# Motherboard.net
KiCad netlist of a schematic drawn in EAGLE
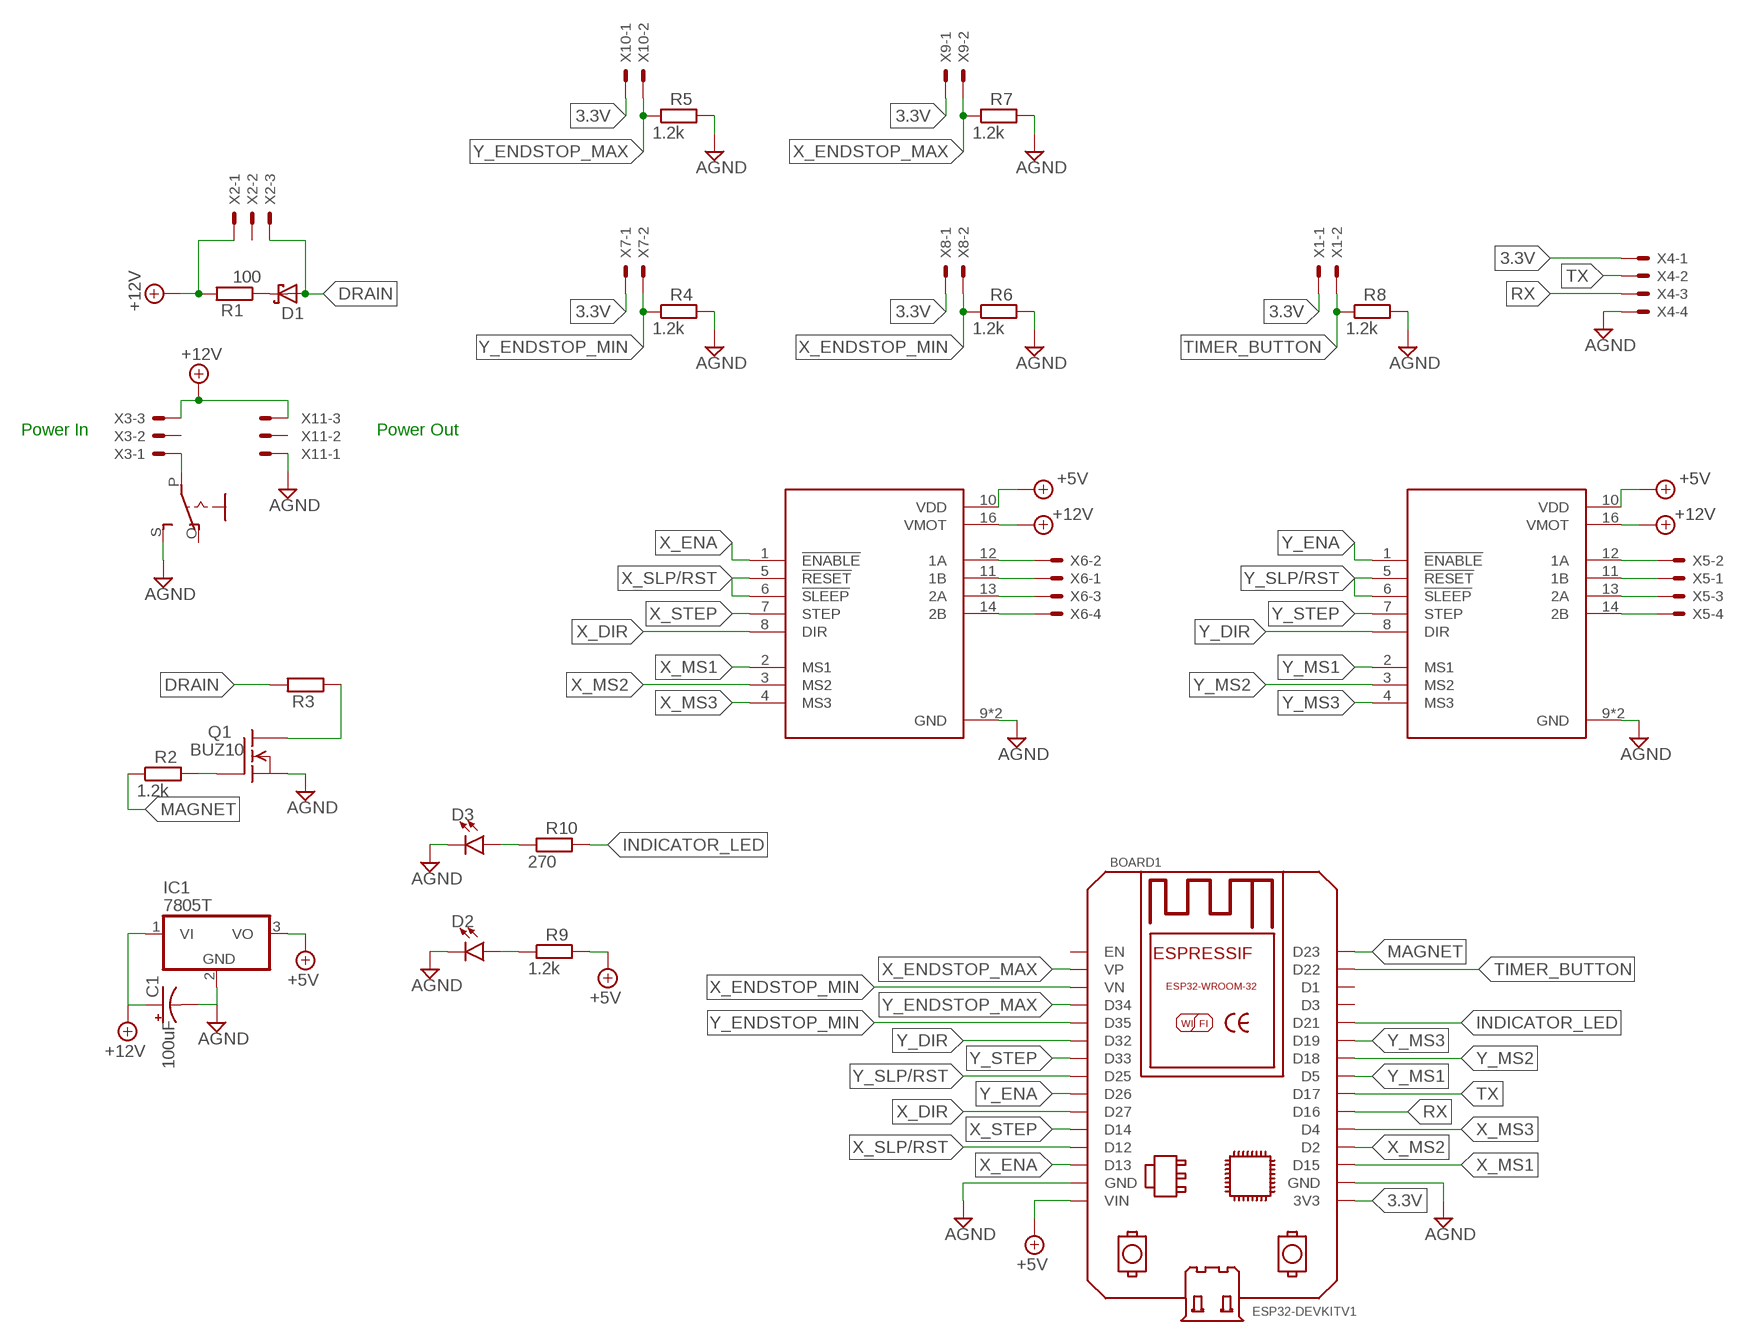
[diagram p0: schematic, sheet 1]

(export (version "E")
  (design (tool "Eeschema 10.0.6"))
  (components
    (comp (ref "BOARD1")
      (value "ESP32DEVKITV1")
      (footprint "eagle-import:ESP32-DEVKITV1")
      (libsource (lib "eagle-import") (part "ESP32DEVKITV1"))
    )
    (comp (ref "C1")
      (value "100uF")
      (footprint "eagle-import:B45181A")
      (libsource (lib "eagle-import") (part "CPOL-USB45181A"))
    )
    (comp (ref "D1")
      (value "SCHOTTKY-DIODEDO41")
      (footprint "eagle-import:DO41-10")
      (libsource (lib "eagle-import") (part "SCHOTTKY-DIODEDO41"))
    )
    (comp (ref "D2")
      (value "LED0603")
      (footprint "eagle-import:LED-0603")
      (libsource (lib "eagle-import") (part "LED0603"))
    )
    (comp (ref "D3")
      (value "LED0603")
      (footprint "eagle-import:LED-0603")
      (libsource (lib "eagle-import") (part "LED0603"))
    )
    (comp (ref "IC1")
      (value "7805T")
      (footprint "eagle-import:TO220H")
      (libsource (lib "eagle-import") (part "78T05"))
    )
    (comp (ref "Q1")
      (value "BUZ10")
      (footprint "eagle-import:TO220")
      (libsource (lib "eagle-import") (part "BUZ10"))
    )
    (comp (ref "R1")
      (value "100")
      (footprint "eagle-import:R0603")
      (libsource (lib "eagle-import") (part "R-EU_R0603"))
    )
    (comp (ref "R2")
      (value "1.2k")
      (footprint "eagle-import:R0603")
      (libsource (lib "eagle-import") (part "R-EU_R0603"))
    )
    (comp (ref "R3")
      (value "R-EU_R0603")
      (footprint "eagle-import:R0603")
      (libsource (lib "eagle-import") (part "R-EU_R0603"))
    )
    (comp (ref "R4")
      (value "1.2k")
      (footprint "eagle-import:R0603")
      (libsource (lib "eagle-import") (part "R-EU_R0603"))
    )
    (comp (ref "R5")
      (value "1.2k")
      (footprint "eagle-import:R0603")
      (libsource (lib "eagle-import") (part "R-EU_R0603"))
    )
    (comp (ref "R6")
      (value "1.2k")
      (footprint "eagle-import:R0603")
      (libsource (lib "eagle-import") (part "R-EU_R0603"))
    )
    (comp (ref "R7")
      (value "1.2k")
      (footprint "eagle-import:R0603")
      (libsource (lib "eagle-import") (part "R-EU_R0603"))
    )
    (comp (ref "R8")
      (value "1.2k")
      (footprint "eagle-import:R0603")
      (libsource (lib "eagle-import") (part "R-EU_R0603"))
    )
    (comp (ref "R9")
      (value "1.2k")
      (footprint "eagle-import:R0603")
      (libsource (lib "eagle-import") (part "R-EU_R0603"))
    )
    (comp (ref "R10")
      (value "270")
      (footprint "eagle-import:R0603")
      (libsource (lib "eagle-import") (part "R-EU_R0603"))
    )
    (comp (ref "S1")
      (value "EG1218S")
      (footprint "eagle-import:EG1218")
      (libsource (lib "eagle-import") (part "EG1218S"))
    )
    (comp (ref "U1")
      (value "A4988_STEPPER_MOTOR_DRIVER_CARRIER")
      (footprint "eagle-import:MODULE_A4988_STEPPER_MOTOR_DRIVER_CARRIER")
      (fields (field (name "MF") "Pololu") (field (name "MP") "A4988 STEPPER MOTOR DRIVER CARRIER"))
      (libsource (lib "eagle-import") (part "A4988_STEPPER_MOTOR_DRIVER_CARRIER"))
    )
    (comp (ref "U2")
      (value "A4988_STEPPER_MOTOR_DRIVER_CARRIER")
      (footprint "eagle-import:MODULE_A4988_STEPPER_MOTOR_DRIVER_CARRIER")
      (fields (field (name "MF") "Pololu") (field (name "MP") "A4988 STEPPER MOTOR DRIVER CARRIER"))
      (libsource (lib "eagle-import") (part "A4988_STEPPER_MOTOR_DRIVER_CARRIER"))
    )
    (comp (ref "X1")
      (value "22-23-2021")
      (footprint "eagle-import:22-23-2021")
      (fields (field (name "MF") "MOLEX"))
      (libsource (lib "eagle-import") (part "22-23-2021"))
    )
    (comp (ref "X2")
      (value "22-23-2031")
      (footprint "eagle-import:22-23-2031")
      (fields (field (name "MF") "MOLEX"))
      (libsource (lib "eagle-import") (part "22-23-2031"))
    )
    (comp (ref "X3")
      (value "22-23-2031")
      (footprint "eagle-import:22-23-2031")
      (fields (field (name "MF") "MOLEX"))
      (libsource (lib "eagle-import") (part "22-23-2031"))
    )
    (comp (ref "X4")
      (value "22-23-2041")
      (footprint "eagle-import:22-23-2041")
      (fields (field (name "MF") "MOLEX"))
      (libsource (lib "eagle-import") (part "22-23-2041"))
    )
    (comp (ref "X5")
      (value "22-23-2041")
      (footprint "eagle-import:22-23-2041")
      (fields (field (name "MF") "MOLEX"))
      (libsource (lib "eagle-import") (part "22-23-2041"))
    )
    (comp (ref "X6")
      (value "22-23-2041")
      (footprint "eagle-import:22-23-2041")
      (fields (field (name "MF") "MOLEX"))
      (libsource (lib "eagle-import") (part "22-23-2041"))
    )
    (comp (ref "X7")
      (value "22-23-2021")
      (footprint "eagle-import:22-23-2021")
      (fields (field (name "MF") "MOLEX"))
      (libsource (lib "eagle-import") (part "22-23-2021"))
    )
    (comp (ref "X8")
      (value "22-23-2021")
      (footprint "eagle-import:22-23-2021")
      (fields (field (name "MF") "MOLEX"))
      (libsource (lib "eagle-import") (part "22-23-2021"))
    )
    (comp (ref "X9")
      (value "22-23-2021")
      (footprint "eagle-import:22-23-2021")
      (fields (field (name "MF") "MOLEX"))
      (libsource (lib "eagle-import") (part "22-23-2021"))
    )
    (comp (ref "X10")
      (value "22-23-2021")
      (footprint "eagle-import:22-23-2021")
      (fields (field (name "MF") "MOLEX"))
      (libsource (lib "eagle-import") (part "22-23-2021"))
    )
    (comp (ref "X11")
      (value "22-23-2031")
      (footprint "eagle-import:22-23-2031")
      (fields (field (name "MF") "MOLEX"))
      (libsource (lib "eagle-import") (part "22-23-2031"))
    )
  )
  (nets
    (net (code "1") (name "+5V") (class "Default")
      (node (ref "BOARD1") (pin "VIN") (pinfunction "VIN_VIN") (pintype "bidirectional"))
      (node (ref "IC1") (pin "3") (pinfunction "VO_3") (pintype "passive"))
      (node (ref "R9") (pin "2") (pinfunction "2_2") (pintype "passive"))
      (node (ref "U1") (pin "10") (pinfunction "VDD_10") (pintype "power_in"))
      (node (ref "U2") (pin "10") (pinfunction "VDD_10") (pintype "power_in"))
    )
    (net (code "2") (name "+12V") (class "Default")
      (node (ref "C1") (pin "+") (pinfunction "+_+") (pintype "passive"))
      (node (ref "IC1") (pin "1") (pinfunction "VI_1") (pintype "input"))
      (node (ref "R1") (pin "2") (pinfunction "2_2") (pintype "passive"))
      (node (ref "U1") (pin "16") (pinfunction "VMOT_16") (pintype "power_in"))
      (node (ref "U2") (pin "16") (pinfunction "VMOT_16") (pintype "power_in"))
      (node (ref "X11") (pin "3") (pinfunction "S_3") (pintype "passive"))
      (node (ref "X2") (pin "1") (pinfunction "S_1") (pintype "passive"))
      (node (ref "X3") (pin "3") (pinfunction "S_3") (pintype "passive"))
    )
    (net (code "3") (name "3.3V") (class "Default")
      (node (ref "BOARD1") (pin "3V3") (pinfunction "3V3_3V3") (pintype "bidirectional"))
      (node (ref "X1") (pin "1") (pinfunction "S_1") (pintype "passive"))
      (node (ref "X10") (pin "1") (pinfunction "S_1") (pintype "passive"))
      (node (ref "X4") (pin "1") (pinfunction "S_1") (pintype "passive"))
      (node (ref "X7") (pin "1") (pinfunction "S_1") (pintype "passive"))
      (node (ref "X8") (pin "1") (pinfunction "S_1") (pintype "passive"))
      (node (ref "X9") (pin "1") (pinfunction "S_1") (pintype "passive"))
    )
    (net (code "4") (name "AGND") (class "Default")
      (node (ref "BOARD1") (pin "GND") (pinfunction "GND_GND") (pintype "bidirectional"))
      (node (ref "BOARD1") (pin "GND@1") (pinfunction "GND_GND@1") (pintype "bidirectional"))
      (node (ref "C1") (pin "-") (pinfunction "-_-") (pintype "passive"))
      (node (ref "D2") (pin "C") (pinfunction "C_C") (pintype "passive"))
      (node (ref "D3") (pin "C") (pinfunction "C_C") (pintype "passive"))
      (node (ref "IC1") (pin "2") (pinfunction "GND_2") (pintype "passive"))
      (node (ref "Q1") (pin "3") (pinfunction "S_3") (pintype "passive"))
      (node (ref "R4") (pin "2") (pinfunction "2_2") (pintype "passive"))
      (node (ref "R5") (pin "2") (pinfunction "2_2") (pintype "passive"))
      (node (ref "R6") (pin "2") (pinfunction "2_2") (pintype "passive"))
      (node (ref "R7") (pin "2") (pinfunction "2_2") (pintype "passive"))
      (node (ref "R8") (pin "2") (pinfunction "2_2") (pintype "passive"))
      (node (ref "S1") (pin "S") (pinfunction "S_S") (pintype "passive"))
      (node (ref "U1") (pin "15") (pinfunction "GND_15") (pintype "power_in"))
      (node (ref "U1") (pin "9") (pinfunction "GND_9") (pintype "power_in"))
      (node (ref "U2") (pin "15") (pinfunction "GND_15") (pintype "power_in"))
      (node (ref "U2") (pin "9") (pinfunction "GND_9") (pintype "power_in"))
      (node (ref "X11") (pin "1") (pinfunction "S_1") (pintype "passive"))
      (node (ref "X4") (pin "4") (pinfunction "S_4") (pintype "passive"))
    )
    (net (code "5") (name "DRAIN") (class "Default")
      (node (ref "D1") (pin "A") (pinfunction "A_A") (pintype "passive"))
      (node (ref "R3") (pin "2") (pinfunction "2_2") (pintype "passive"))
      (node (ref "X2") (pin "3") (pinfunction "S_3") (pintype "passive"))
    )
    (net (code "6") (name "INDICATOR_LED") (class "Default")
      (node (ref "BOARD1") (pin "D21") (pinfunction "D21_D21") (pintype "bidirectional"))
      (node (ref "R10") (pin "2") (pinfunction "2_2") (pintype "passive"))
    )
    (net (code "7") (name "MAGNET") (class "Default")
      (node (ref "BOARD1") (pin "D23") (pinfunction "D23_D23") (pintype "bidirectional"))
      (node (ref "R2") (pin "1") (pinfunction "1_1") (pintype "passive"))
    )
    (net (code "8") (name "Net-(D1-PadC)") (class "Default")
      (node (ref "D1") (pin "C") (pinfunction "C_C") (pintype "passive"))
      (node (ref "R1") (pin "1") (pinfunction "1_1") (pintype "passive"))
    )
    (net (code "9") (name "Net-(D2-PadA)") (class "Default")
      (node (ref "D2") (pin "A") (pinfunction "A_A") (pintype "passive"))
      (node (ref "R9") (pin "1") (pinfunction "1_1") (pintype "passive"))
    )
    (net (code "10") (name "Net-(D3-PadA)") (class "Default")
      (node (ref "D3") (pin "A") (pinfunction "A_A") (pintype "passive"))
      (node (ref "R10") (pin "1") (pinfunction "1_1") (pintype "passive"))
    )
    (net (code "11") (name "Net-(Q1-D)") (class "Default")
      (node (ref "Q1") (pin "2") (pinfunction "D_2") (pintype "passive"))
      (node (ref "R3") (pin "1") (pinfunction "1_1") (pintype "passive"))
    )
    (net (code "12") (name "Net-(Q1-G)") (class "Default")
      (node (ref "Q1") (pin "1") (pinfunction "G_1") (pintype "passive"))
      (node (ref "R2") (pin "2") (pinfunction "2_2") (pintype "passive"))
    )
    (net (code "13") (name "Net-(U1-1A)") (class "Default")
      (node (ref "U1") (pin "12") (pinfunction "1A_12") (pintype "output"))
      (node (ref "X6") (pin "2") (pinfunction "S_2") (pintype "passive"))
    )
    (net (code "14") (name "Net-(U1-1B)") (class "Default")
      (node (ref "U1") (pin "11") (pinfunction "1B_11") (pintype "output"))
      (node (ref "X6") (pin "1") (pinfunction "S_1") (pintype "passive"))
    )
    (net (code "15") (name "Net-(U1-2A)") (class "Default")
      (node (ref "U1") (pin "13") (pinfunction "2A_13") (pintype "output"))
      (node (ref "X6") (pin "3") (pinfunction "S_3") (pintype "passive"))
    )
    (net (code "16") (name "Net-(U1-2B)") (class "Default")
      (node (ref "U1") (pin "14") (pinfunction "2B_14") (pintype "output"))
      (node (ref "X6") (pin "4") (pinfunction "S_4") (pintype "passive"))
    )
    (net (code "17") (name "Net-(U2-1A)") (class "Default")
      (node (ref "U2") (pin "12") (pinfunction "1A_12") (pintype "output"))
      (node (ref "X5") (pin "2") (pinfunction "S_2") (pintype "passive"))
    )
    (net (code "18") (name "Net-(U2-1B)") (class "Default")
      (node (ref "U2") (pin "11") (pinfunction "1B_11") (pintype "output"))
      (node (ref "X5") (pin "1") (pinfunction "S_1") (pintype "passive"))
    )
    (net (code "19") (name "Net-(U2-2A)") (class "Default")
      (node (ref "U2") (pin "13") (pinfunction "2A_13") (pintype "output"))
      (node (ref "X5") (pin "3") (pinfunction "S_3") (pintype "passive"))
    )
    (net (code "20") (name "Net-(U2-2B)") (class "Default")
      (node (ref "U2") (pin "14") (pinfunction "2B_14") (pintype "output"))
      (node (ref "X5") (pin "4") (pinfunction "S_4") (pintype "passive"))
    )
    (net (code "21") (name "Net-(X3A-S)") (class "Default")
      (node (ref "S1") (pin "P") (pinfunction "P_P") (pintype "passive"))
      (node (ref "X3") (pin "1") (pinfunction "S_1") (pintype "passive"))
    )
    (net (code "22") (name "RX") (class "Default")
      (node (ref "BOARD1") (pin "D16") (pinfunction "D16_D16") (pintype "bidirectional"))
      (node (ref "X4") (pin "3") (pinfunction "S_3") (pintype "passive"))
    )
    (net (code "23") (name "TIMER_BUTTON") (class "Default")
      (node (ref "BOARD1") (pin "D22") (pinfunction "D22_D22") (pintype "bidirectional"))
      (node (ref "R8") (pin "1") (pinfunction "1_1") (pintype "passive"))
      (node (ref "X1") (pin "2") (pinfunction "S_2") (pintype "passive"))
    )
    (net (code "24") (name "TX") (class "Default")
      (node (ref "BOARD1") (pin "D17") (pinfunction "D17_D17") (pintype "bidirectional"))
      (node (ref "X4") (pin "2") (pinfunction "S_2") (pintype "passive"))
    )
    (net (code "25") (name "X_DIR") (class "Default")
      (node (ref "BOARD1") (pin "D27") (pinfunction "D27_D27") (pintype "bidirectional"))
      (node (ref "U1") (pin "8") (pinfunction "DIR_8") (pintype "input"))
    )
    (net (code "26") (name "X_ENA") (class "Default")
      (node (ref "BOARD1") (pin "D13") (pinfunction "D13_D13") (pintype "bidirectional"))
      (node (ref "U1") (pin "1") (pinfunction "~{ENABLE}_1") (pintype "input"))
    )
    (net (code "27") (name "X_ENDSTOP_MAX") (class "Default")
      (node (ref "BOARD1") (pin "VP") (pinfunction "VP_VP") (pintype "bidirectional"))
      (node (ref "R7") (pin "1") (pinfunction "1_1") (pintype "passive"))
      (node (ref "X9") (pin "2") (pinfunction "S_2") (pintype "passive"))
    )
    (net (code "28") (name "X_ENDSTOP_MIN") (class "Default")
      (node (ref "BOARD1") (pin "VN") (pinfunction "VN_VN") (pintype "bidirectional"))
      (node (ref "R6") (pin "1") (pinfunction "1_1") (pintype "passive"))
      (node (ref "X8") (pin "2") (pinfunction "S_2") (pintype "passive"))
    )
    (net (code "29") (name "X_MS1") (class "Default")
      (node (ref "BOARD1") (pin "D15") (pinfunction "D15_D15") (pintype "bidirectional"))
      (node (ref "U1") (pin "2") (pinfunction "MS1_2") (pintype "input"))
    )
    (net (code "30") (name "X_MS2") (class "Default")
      (node (ref "BOARD1") (pin "D2") (pinfunction "D2_D2") (pintype "bidirectional"))
      (node (ref "U1") (pin "3") (pinfunction "MS2_3") (pintype "input"))
    )
    (net (code "31") (name "X_MS3") (class "Default")
      (node (ref "BOARD1") (pin "D4") (pinfunction "D4_D4") (pintype "bidirectional"))
      (node (ref "U1") (pin "4") (pinfunction "MS3_4") (pintype "input"))
    )
    (net (code "32") (name "X_SLP{slash}RST") (class "Default")
      (node (ref "BOARD1") (pin "D12") (pinfunction "D12_D12") (pintype "bidirectional"))
      (node (ref "U1") (pin "5") (pinfunction "~{RESET}_5") (pintype "input"))
      (node (ref "U1") (pin "6") (pinfunction "~{SLEEP}_6") (pintype "input"))
    )
    (net (code "33") (name "X_STEP") (class "Default")
      (node (ref "BOARD1") (pin "D14") (pinfunction "D14_D14") (pintype "bidirectional"))
      (node (ref "U1") (pin "7") (pinfunction "STEP_7") (pintype "input"))
    )
    (net (code "34") (name "Y_DIR") (class "Default")
      (node (ref "BOARD1") (pin "D32") (pinfunction "D32_D32") (pintype "bidirectional"))
      (node (ref "U2") (pin "8") (pinfunction "DIR_8") (pintype "input"))
    )
    (net (code "35") (name "Y_ENA") (class "Default")
      (node (ref "BOARD1") (pin "D26") (pinfunction "D26_D26") (pintype "bidirectional"))
      (node (ref "U2") (pin "1") (pinfunction "~{ENABLE}_1") (pintype "input"))
    )
    (net (code "36") (name "Y_ENDSTOP_MAX") (class "Default")
      (node (ref "BOARD1") (pin "D34") (pinfunction "D34_D34") (pintype "bidirectional"))
      (node (ref "R5") (pin "1") (pinfunction "1_1") (pintype "passive"))
      (node (ref "X10") (pin "2") (pinfunction "S_2") (pintype "passive"))
    )
    (net (code "37") (name "Y_ENDSTOP_MIN") (class "Default")
      (node (ref "BOARD1") (pin "D35") (pinfunction "D35_D35") (pintype "bidirectional"))
      (node (ref "R4") (pin "1") (pinfunction "1_1") (pintype "passive"))
      (node (ref "X7") (pin "2") (pinfunction "S_2") (pintype "passive"))
    )
    (net (code "38") (name "Y_MS1") (class "Default")
      (node (ref "BOARD1") (pin "D5") (pinfunction "D5_D5") (pintype "bidirectional"))
      (node (ref "U2") (pin "2") (pinfunction "MS1_2") (pintype "input"))
    )
    (net (code "39") (name "Y_MS2") (class "Default")
      (node (ref "BOARD1") (pin "D18") (pinfunction "D18_D18") (pintype "bidirectional"))
      (node (ref "U2") (pin "3") (pinfunction "MS2_3") (pintype "input"))
    )
    (net (code "40") (name "Y_MS3") (class "Default")
      (node (ref "BOARD1") (pin "D19") (pinfunction "D19_D19") (pintype "bidirectional"))
      (node (ref "U2") (pin "4") (pinfunction "MS3_4") (pintype "input"))
    )
    (net (code "41") (name "Y_SLP{slash}RST") (class "Default")
      (node (ref "BOARD1") (pin "D25") (pinfunction "D25_D25") (pintype "bidirectional"))
      (node (ref "U2") (pin "5") (pinfunction "~{RESET}_5") (pintype "input"))
      (node (ref "U2") (pin "6") (pinfunction "~{SLEEP}_6") (pintype "input"))
    )
    (net (code "42") (name "Y_STEP") (class "Default")
      (node (ref "BOARD1") (pin "D33") (pinfunction "D33_D33") (pintype "bidirectional"))
      (node (ref "U2") (pin "7") (pinfunction "STEP_7") (pintype "input"))
    )
    (net (code "43") (name "unconnected-(BOARD1-PadD1)") (class "Default")
      (node (ref "BOARD1") (pin "D1") (pinfunction "D1_D1") (pintype "bidirectional"))
    )
    (net (code "44") (name "unconnected-(BOARD1-PadD3)") (class "Default")
      (node (ref "BOARD1") (pin "D3") (pinfunction "D3_D3") (pintype "bidirectional"))
    )
    (net (code "45") (name "unconnected-(BOARD1-PadEN)") (class "Default")
      (node (ref "BOARD1") (pin "EN") (pinfunction "EN_EN") (pintype "bidirectional"))
    )
    (net (code "46") (name "unconnected-(S1-PadO)") (class "Default")
      (node (ref "S1") (pin "O") (pinfunction "O_O") (pintype "passive"))
    )
    (net (code "47") (name "unconnected-(X2B-S-Pad2)") (class "Default")
      (node (ref "X2") (pin "2") (pinfunction "S_2") (pintype "passive"))
    )
    (net (code "48") (name "unconnected-(X3B-S-Pad2)") (class "Default")
      (node (ref "X3") (pin "2") (pinfunction "S_2") (pintype "passive"))
    )
    (net (code "49") (name "unconnected-(X11B-S-Pad2)") (class "Default")
      (node (ref "X11") (pin "2") (pinfunction "S_2") (pintype "passive"))
    )
  )
)
